# Temperature_Sensor_Rev_3.net
KiCad netlist of a schematic drawn in EAGLE
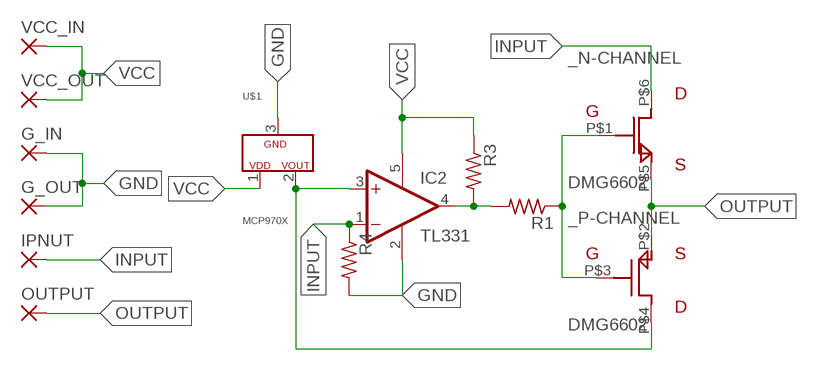
[diagram p0: schematic, sheet 1]

(export (version "E")
  (design (tool "Eeschema 10.0.6"))
  (components
    (comp (ref "G_IN")
      (value "1,6/0,8")
      (footprint "eagle-import:1,6_0,8")
      (libsource (lib "eagle-import") (part "1,6/0,8"))
    )
    (comp (ref "G_OUT")
      (value "1,6/0,8")
      (footprint "eagle-import:1,6_0,8")
      (libsource (lib "eagle-import") (part "1,6/0,8"))
    )
    (comp (ref "IC2")
      (value "TL331")
      (footprint "eagle-import:DBV-R-PDSO-G5")
      (libsource (lib "eagle-import") (part "TL331"))
    )
    (comp (ref "IPNUT")
      (value "1,6/0,8")
      (footprint "eagle-import:1,6_0,8")
      (libsource (lib "eagle-import") (part "1,6/0,8"))
    )
    (comp (ref "OUTPUT")
      (value "1,6/0,8")
      (footprint "eagle-import:1,6_0,8")
      (libsource (lib "eagle-import") (part "1,6/0,8"))
    )
    (comp (ref "R1")
      (value "R-US_R0603")
      (footprint "eagle-import:R0603")
      (libsource (lib "eagle-import") (part "R-US_R0603"))
    )
    (comp (ref "R3")
      (value "R-US_R0603")
      (footprint "eagle-import:R0603")
      (libsource (lib "eagle-import") (part "R-US_R0603"))
    )
    (comp (ref "R4")
      (value "R-US_R0603")
      (footprint "eagle-import:R0603")
      (libsource (lib "eagle-import") (part "R-US_R0603"))
    )
    (comp (ref "U$1")
      (value "MCP970X")
      (footprint "eagle-import:SOT23")
      (libsource (lib "eagle-import") (part "MCP970X"))
    )
    (comp (ref "VCC_IN")
      (value "1,6/0,8")
      (footprint "eagle-import:1,6_0,8")
      (libsource (lib "eagle-import") (part "1,6/0,8"))
    )
    (comp (ref "VCC_OUT")
      (value "1,6/0,8")
      (footprint "eagle-import:1,6_0,8")
      (libsource (lib "eagle-import") (part "1,6/0,8"))
    )
    (comp (ref "_")
      (value "DMG6602")
      (footprint "eagle-import:SOT23-6")
      (libsource (lib "eagle-import") (part "DMG6602"))
    )
  )
  (nets
    (net (code "1") (name "GND") (class "Default")
      (node (ref "G_IN") (pin "1") (pinfunction "P_1") (pintype "passive"))
      (node (ref "G_OUT") (pin "1") (pinfunction "P_1") (pintype "passive"))
      (node (ref "IC2") (pin "2") (pinfunction "GND_2") (pintype "power_in"))
      (node (ref "R4") (pin "2") (pinfunction "2_2") (pintype "passive"))
      (node (ref "U$1") (pin "3") (pinfunction "GND_3") (pintype "bidirectional"))
    )
    (net (code "2") (name "INPUT") (class "Default")
      (node (ref "IC2") (pin "1") (pinfunction "-IN_1") (pintype "input"))
      (node (ref "IPNUT") (pin "1") (pinfunction "P_1") (pintype "passive"))
      (node (ref "R4") (pin "1") (pinfunction "1_1") (pintype "passive"))
      (node (ref "_") (pin "P$6") (pinfunction "D$1_P$6") (pintype "bidirectional"))
    )
    (net (code "3") (name "Net-(IC2-+IN)") (class "Default")
      (node (ref "IC2") (pin "3") (pinfunction "+IN_3") (pintype "input"))
      (node (ref "U$1") (pin "2") (pinfunction "VOUT_2") (pintype "bidirectional"))
      (node (ref "_") (pin "P$4") (pinfunction "D$1_P$4") (pintype "bidirectional"))
    )
    (net (code "4") (name "Net-(IC2-OUT)") (class "Default")
      (node (ref "IC2") (pin "4") (pinfunction "OUT_4") (pintype "output"))
      (node (ref "R1") (pin "2") (pinfunction "2_2") (pintype "passive"))
      (node (ref "R3") (pin "2") (pinfunction "2_2") (pintype "passive"))
    )
    (net (code "5") (name "Net-(_A-G$1)") (class "Default")
      (node (ref "R1") (pin "1") (pinfunction "1_1") (pintype "passive"))
      (node (ref "_") (pin "P$1") (pinfunction "G$1_P$1") (pintype "bidirectional"))
      (node (ref "_") (pin "P$3") (pinfunction "G$1_P$3") (pintype "bidirectional"))
    )
    (net (code "6") (name "OUTPUT") (class "Default")
      (node (ref "OUTPUT") (pin "1") (pinfunction "P_1") (pintype "passive"))
      (node (ref "_") (pin "P$2") (pinfunction "S$1_P$2") (pintype "bidirectional"))
      (node (ref "_") (pin "P$5") (pinfunction "S$1_P$5") (pintype "bidirectional"))
    )
    (net (code "7") (name "VCC") (class "Default")
      (node (ref "IC2") (pin "5") (pinfunction "V+_5") (pintype "power_in"))
      (node (ref "R3") (pin "1") (pinfunction "1_1") (pintype "passive"))
      (node (ref "U$1") (pin "1") (pinfunction "VDD_1") (pintype "bidirectional"))
      (node (ref "VCC_IN") (pin "1") (pinfunction "P_1") (pintype "passive"))
      (node (ref "VCC_OUT") (pin "1") (pinfunction "P_1") (pintype "passive"))
    )
  )
)
